# Joystick.net
KiCad netlist of a schematic drawn in EAGLE
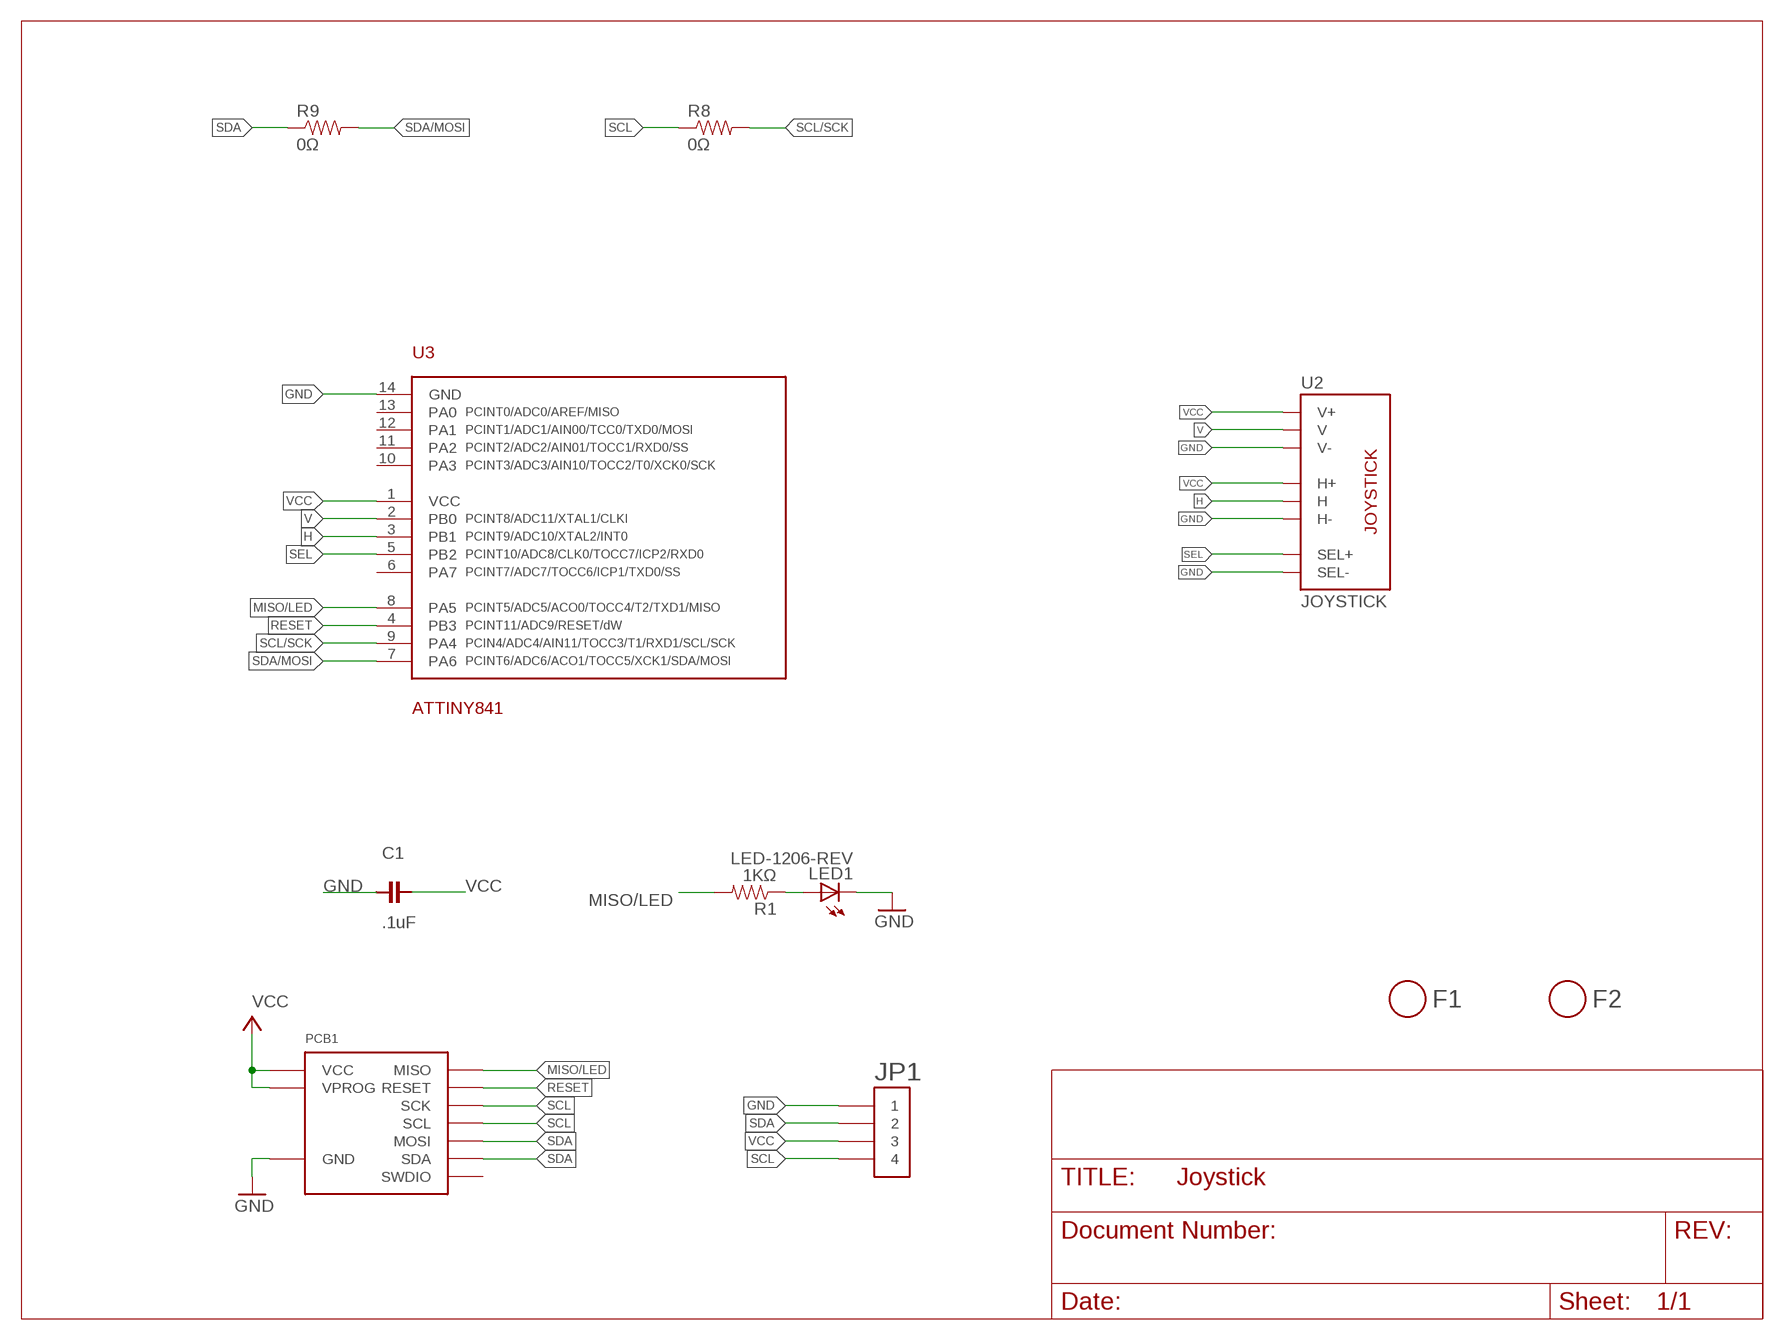
[diagram p0: schematic, sheet 1]

(export (version "E")
  (design (tool "Eeschema 10.0.6"))
  (components
    (comp (ref "C1")
      (value ".1uF")
      (footprint "eagle-import:0603")
      (fields (field (name "PARTNUM") "C0603C104K5RACTU"))
      (libsource (lib "eagle-import") (part "CAPACITOR-.1UF"))
    )
    (comp (ref "F1")
      (value "FIDUCIAL")
      (footprint "eagle-import:FIDUCIAL_1MM")
      (fields (field (name "BOM") "EXCLUDE"))
      (libsource (lib "eagle-import") (part "FIDUCIAL"))
    )
    (comp (ref "F2")
      (value "FIDUCIAL")
      (footprint "eagle-import:FIDUCIAL_1MM")
      (fields (field (name "BOM") "EXCLUDE"))
      (libsource (lib "eagle-import") (part "FIDUCIAL"))
    )
    (comp (ref "JP1")
      (value "HEADER-1X4-AMPMODU")
      (footprint "eagle-import:AMPMODU-4P")
      (fields (field (name "PARTNUM") "147721-3"))
      (libsource (lib "eagle-import") (part "HEADER-1X4-AMPMODU"))
    )
    (comp (ref "LED1")
      (value "LED-1206-REV")
      (footprint "eagle-import:LED-1206-REV")
      (fields (field (name "PARTNUM") "LTST-C230TBKT"))
      (libsource (lib "eagle-import") (part "LED-1206-REV"))
    )
    (comp (ref "PCB1")
      (value "DEVICE-PCB")
      (footprint "eagle-import:DEVICE-PCB")
      (fields (field (name "PARTNUM") "Joystick PCB"))
      (libsource (lib "eagle-import") (part "DEVICE-PCB"))
    )
    (comp (ref "R1")
      (value "1KΩ")
      (footprint "eagle-import:0603")
      (fields (field (name "PARTNUM") "ERJ-3EKF1001V"))
      (libsource (lib "eagle-import") (part "RESISTOR-1KΩ"))
    )
    (comp (ref "R8")
      (value "0Ω")
      (footprint "eagle-import:0603")
      (fields (field (name "PARTNUM") "ERJ-3GEY0R00V"))
      (libsource (lib "eagle-import") (part "RESISTOR-0Ω"))
    )
    (comp (ref "R9")
      (value "0Ω")
      (footprint "eagle-import:0603")
      (fields (field (name "PARTNUM") "ERJ-3GEY0R00V"))
      (libsource (lib "eagle-import") (part "RESISTOR-0Ω"))
    )
    (comp (ref "U2")
      (value "JOYSTICK")
      (footprint "eagle-import:JOYSTICK")
      (fields (field (name "PARTNUM") "Joystick"))
      (libsource (lib "eagle-import") (part "JOYSTICK"))
    )
    (comp (ref "U3")
      (value "ATTINY841")
      (footprint "eagle-import:SOIC-14")
      (fields (field (name "PARTNUM") "ATTINY841-SSUR"))
      (libsource (lib "eagle-import") (part "ATTINY841"))
    )
  )
  (nets
    (net (code "1") (name "GND") (class "Default")
      (node (ref "C1") (pin "2") (pinfunction "2_2") (pintype "passive"))
      (node (ref "JP1") (pin "P$1") (pinfunction "1_P$1") (pintype "bidirectional"))
      (node (ref "JP1") (pin "P$2") (pinfunction "1_P$2") (pintype "bidirectional"))
      (node (ref "LED1") (pin "C") (pinfunction "C_C") (pintype "passive"))
      (node (ref "PCB1") (pin "GND") (pinfunction "GND_GND") (pintype "bidirectional"))
      (node (ref "U2") (pin "B2A") (pinfunction "SEL-_B2A") (pintype "bidirectional"))
      (node (ref "U2") (pin "H3") (pinfunction "H-_H3") (pintype "bidirectional"))
      (node (ref "U2") (pin "V3") (pinfunction "V-_V3") (pintype "bidirectional"))
      (node (ref "U3") (pin "14") (pinfunction "GND_14") (pintype "bidirectional"))
    )
    (net (code "2") (name "H") (class "Default")
      (node (ref "U2") (pin "H2") (pinfunction "H_H2") (pintype "bidirectional"))
      (node (ref "U3") (pin "3") (pinfunction "PB1_3") (pintype "bidirectional"))
    )
    (net (code "3") (name "MISO{slash}LED") (class "Default")
      (node (ref "PCB1") (pin "MISO") (pinfunction "MISO_MISO") (pintype "bidirectional"))
      (node (ref "R1") (pin "2") (pinfunction "2_2") (pintype "passive"))
      (node (ref "U3") (pin "8") (pinfunction "PA5_8") (pintype "bidirectional"))
    )
    (net (code "4") (name "Net-(LED1-PadA)") (class "Default")
      (node (ref "LED1") (pin "A") (pinfunction "A_A") (pintype "passive"))
      (node (ref "R1") (pin "1") (pinfunction "1_1") (pintype "passive"))
    )
    (net (code "5") (name "RESET") (class "Default")
      (node (ref "PCB1") (pin "RESET") (pinfunction "RESET_RESET") (pintype "bidirectional"))
      (node (ref "U3") (pin "4") (pinfunction "PB3_4") (pintype "bidirectional"))
    )
    (net (code "6") (name "SCL") (class "Default")
      (node (ref "JP1") (pin "P$7") (pinfunction "4_P$7") (pintype "bidirectional"))
      (node (ref "JP1") (pin "P$8") (pinfunction "4_P$8") (pintype "bidirectional"))
      (node (ref "PCB1") (pin "CLK") (pinfunction "SCK_CLK") (pintype "bidirectional"))
      (node (ref "PCB1") (pin "SCL") (pinfunction "SCL_SCL") (pintype "bidirectional"))
      (node (ref "R8") (pin "1") (pinfunction "1_1") (pintype "passive"))
    )
    (net (code "7") (name "SCL{slash}SCK") (class "Default")
      (node (ref "R8") (pin "2") (pinfunction "2_2") (pintype "passive"))
      (node (ref "U3") (pin "9") (pinfunction "PA4_9") (pintype "bidirectional"))
    )
    (net (code "8") (name "SDA") (class "Default")
      (node (ref "JP1") (pin "P$3") (pinfunction "2_P$3") (pintype "bidirectional"))
      (node (ref "JP1") (pin "P$4") (pinfunction "2_P$4") (pintype "bidirectional"))
      (node (ref "PCB1") (pin "MOSI") (pinfunction "MOSI_MOSI") (pintype "bidirectional"))
      (node (ref "PCB1") (pin "SDA") (pinfunction "SDA_SDA") (pintype "bidirectional"))
      (node (ref "R9") (pin "1") (pinfunction "1_1") (pintype "passive"))
    )
    (net (code "9") (name "SDA{slash}MOSI") (class "Default")
      (node (ref "R9") (pin "2") (pinfunction "2_2") (pintype "passive"))
      (node (ref "U3") (pin "7") (pinfunction "PA6_7") (pintype "bidirectional"))
    )
    (net (code "10") (name "SEL") (class "Default")
      (node (ref "U2") (pin "B1A") (pinfunction "SEL+_B1A") (pintype "bidirectional"))
      (node (ref "U3") (pin "5") (pinfunction "PB2_5") (pintype "bidirectional"))
    )
    (net (code "11") (name "V") (class "Default")
      (node (ref "U2") (pin "V2") (pinfunction "V_V2") (pintype "bidirectional"))
      (node (ref "U3") (pin "2") (pinfunction "PB0_2") (pintype "bidirectional"))
    )
    (net (code "12") (name "VCC") (class "Default")
      (node (ref "C1") (pin "1") (pinfunction "1_1") (pintype "passive"))
      (node (ref "JP1") (pin "P$5") (pinfunction "3_P$5") (pintype "bidirectional"))
      (node (ref "JP1") (pin "P$6") (pinfunction "3_P$6") (pintype "bidirectional"))
      (node (ref "PCB1") (pin "VCC") (pinfunction "VCC_VCC") (pintype "bidirectional"))
      (node (ref "PCB1") (pin "VPROG") (pinfunction "VPROG_VPROG") (pintype "bidirectional"))
      (node (ref "U2") (pin "H1") (pinfunction "H+_H1") (pintype "bidirectional"))
      (node (ref "U2") (pin "V1") (pinfunction "V+_V1") (pintype "bidirectional"))
      (node (ref "U3") (pin "1") (pinfunction "VCC_1") (pintype "bidirectional"))
    )
    (net (code "13") (name "unconnected-(PCB1-PadSWDIO)") (class "Default")
      (node (ref "PCB1") (pin "SWDIO") (pinfunction "SWDIO_SWDIO") (pintype "bidirectional"))
    )
    (net (code "14") (name "unconnected-(U3-PA0-Pad13)") (class "Default")
      (node (ref "U3") (pin "13") (pinfunction "PA0_13") (pintype "bidirectional"))
    )
    (net (code "15") (name "unconnected-(U3-PA1-Pad12)") (class "Default")
      (node (ref "U3") (pin "12") (pinfunction "PA1_12") (pintype "bidirectional"))
    )
    (net (code "16") (name "unconnected-(U3-PA2-Pad11)") (class "Default")
      (node (ref "U3") (pin "11") (pinfunction "PA2_11") (pintype "bidirectional"))
    )
    (net (code "17") (name "unconnected-(U3-PA3-Pad10)") (class "Default")
      (node (ref "U3") (pin "10") (pinfunction "PA3_10") (pintype "bidirectional"))
    )
    (net (code "18") (name "unconnected-(U3-PA7-Pad6)") (class "Default")
      (node (ref "U3") (pin "6") (pinfunction "PA7_6") (pintype "bidirectional"))
    )
  )
)
